# SCH_USB-hub-version-2_2024-07-09.net
KiCad netlist of a schematic drawn in EasyEDA
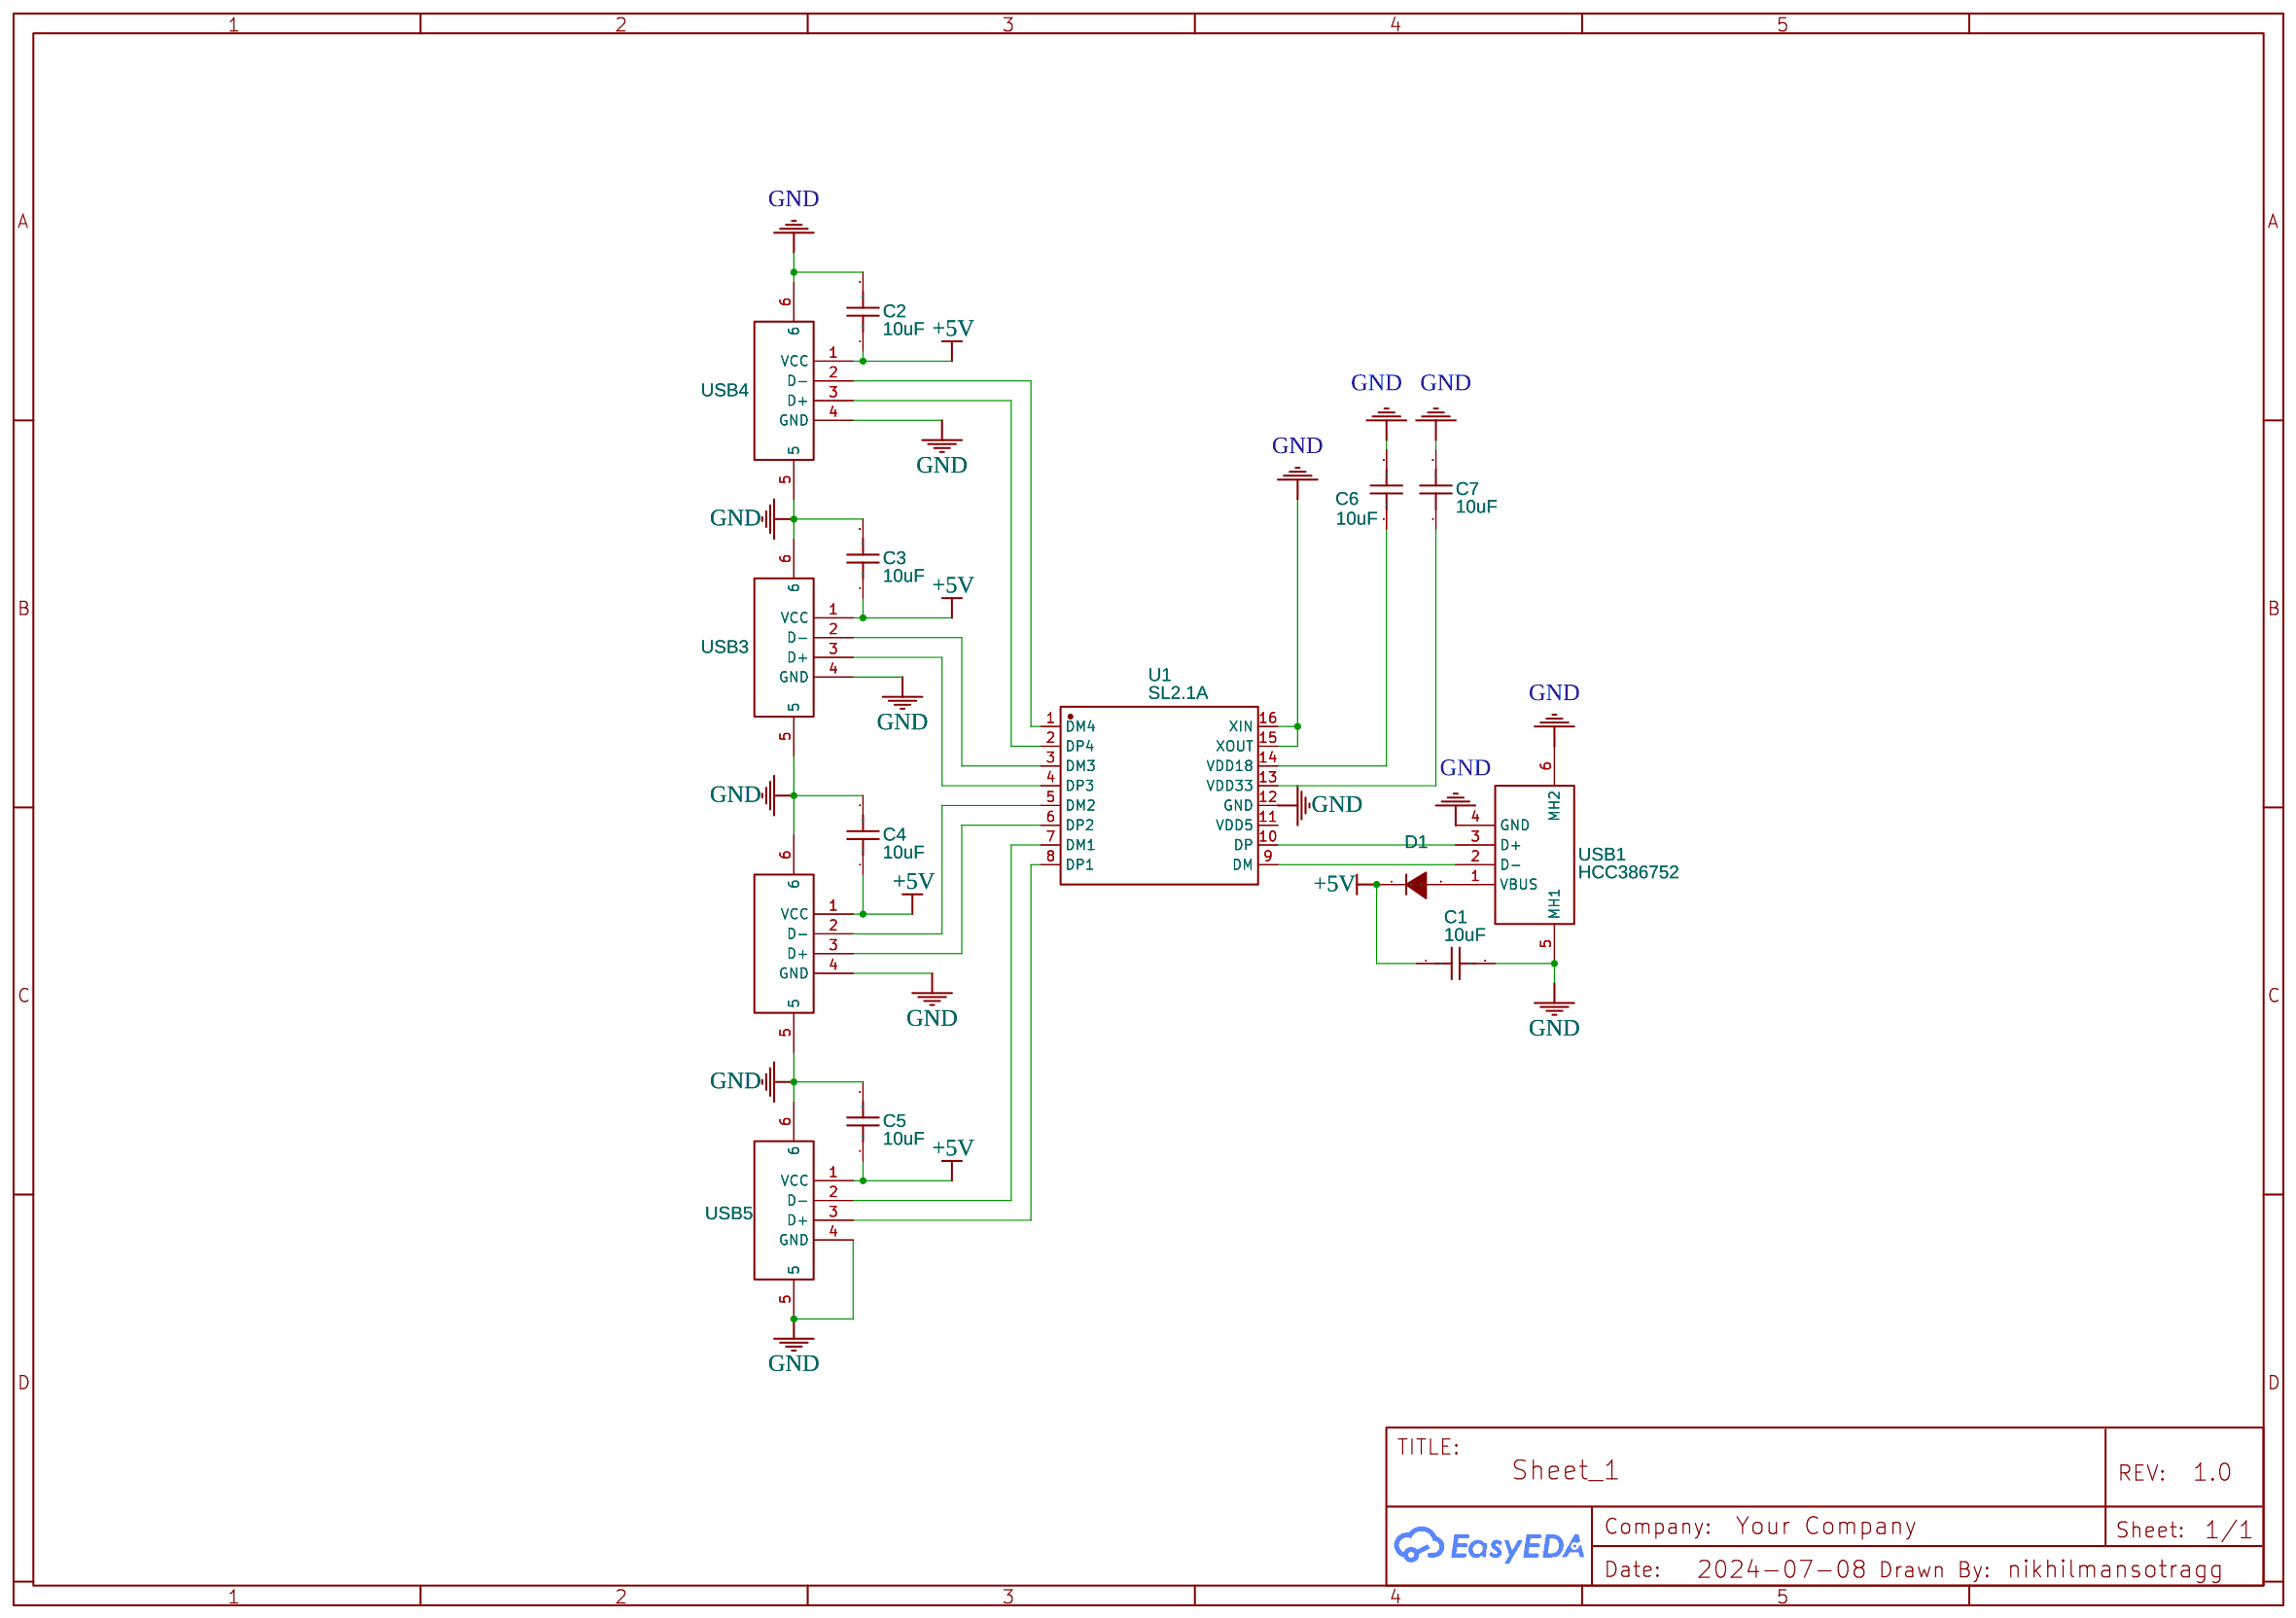
[diagram p0: schematic sheet]

(export (version "E")
  (design (tool "Eeschema 10.0.6"))
  (components
    (comp (ref "C1")
      (value "10uF")
      (fields
        (field (name "Manufacturer Part") "CL10A106KP8NNNC")
        (field (name "Manufacturer") "SAMSUNG(三星)")
      )
      (libsource (lib "") (part "CL10A106KP8NNNC_1"))
    )
    (comp (ref "C2")
      (value "10uF")
      (fields
        (field (name "Manufacturer Part") "CL10A106KP8NNNC")
        (field (name "Manufacturer") "SAMSUNG(三星)")
      )
      (libsource (lib "") (part "CL10A106KP8NNNC"))
    )
    (comp (ref "C3")
      (value "10uF")
      (fields
        (field (name "Manufacturer Part") "CL10A106KP8NNNC")
        (field (name "Manufacturer") "SAMSUNG(三星)")
      )
      (libsource (lib "") (part "CL10A106KP8NNNC"))
    )
    (comp (ref "C4")
      (value "10uF")
      (fields
        (field (name "Manufacturer Part") "CL10A106KP8NNNC")
        (field (name "Manufacturer") "SAMSUNG(三星)")
      )
      (libsource (lib "") (part "CL10A106KP8NNNC"))
    )
    (comp (ref "C5")
      (value "10uF")
      (fields
        (field (name "Manufacturer Part") "CL10A106KP8NNNC")
        (field (name "Manufacturer") "SAMSUNG(三星)")
      )
      (libsource (lib "") (part "CL10A106KP8NNNC"))
    )
    (comp (ref "C6")
      (value "10uF")
      (fields
        (field (name "Manufacturer Part") "CL10A106KP8NNNC")
        (field (name "Manufacturer") "SAMSUNG(三星)")
      )
      (libsource (lib "") (part "CL10A106KP8NNNC"))
    )
    (comp (ref "C7")
      (value "10uF")
      (fields
        (field (name "Manufacturer Part") "CL10A106KP8NNNC")
        (field (name "Manufacturer") "SAMSUNG(三星)")
      )
      (libsource (lib "") (part "CL10A106KP8NNNC"))
    )
    (comp (ref "D1")
      (value "NSR0320MW2T1G")
      (fields (field (name "Manufacturer") "onsemi(安森美)"))
      (libsource (lib "") (part "NSR0320MW2T1G"))
    )
    (comp (ref "U1")
      (value "SL2.1A")
      (fields (field (name "Manufacturer") "CoreChips(和芯润德)"))
      (libsource (lib "") (part "SL2.1A"))
    )
    (comp (ref "USB1")
      (value "HCC386752")
      (fields (field (name "Manufacturer Part") "U-USBAR04P-M003") (field (name "Manufacturer") "Ckmtw(灿科盟)"))
      (libsource (lib "") (part "HCC386752"))
    )
    (comp (ref "USB2")
      (value "USB-AF-90-14.4X13.6-H7.0-DIP")
      (fields (field (name "Manufacturer Part") "903-131A1011D10100") (field (name "Manufacturer") "精拓金"))
      (libsource (lib "") (part "USB-AF-90-14.4X13.6-H7.0-DIP"))
    )
    (comp (ref "USB3")
      (value "USB-AF-90-14.4X13.6-H7.0-DIP")
      (fields (field (name "Manufacturer Part") "903-131A1011D10100") (field (name "Manufacturer") "精拓金"))
      (libsource (lib "") (part "USB-AF-90-14.4X13.6-H7.0-DIP"))
    )
    (comp (ref "USB4")
      (value "USB-AF-90-14.4X13.6-H7.0-DIP")
      (fields (field (name "Manufacturer Part") "903-131A1011D10100") (field (name "Manufacturer") "精拓金"))
      (libsource (lib "") (part "USB-AF-90-14.4X13.6-H7.0-DIP"))
    )
    (comp (ref "USB5")
      (value "USB-AF-90-14.4X13.6-H7.0-DIP")
      (fields (field (name "Manufacturer Part") "903-131A1011D10100") (field (name "Manufacturer") "精拓金"))
      (libsource (lib "") (part "USB-AF-90-14.4X13.6-H7.0-DIP"))
    )
  )
  (nets
    (net (code "1") (name "+5V") (class "Default")
      (node (ref "C1") (pin "1") (pinfunction "1_1") (pintype "unspecified"))
      (node (ref "C2") (pin "1") (pinfunction "1_1") (pintype "unspecified"))
      (node (ref "C3") (pin "1") (pinfunction "1_1") (pintype "unspecified"))
      (node (ref "C4") (pin "1") (pinfunction "1_1") (pintype "unspecified"))
      (node (ref "C5") (pin "1") (pinfunction "1_1") (pintype "unspecified"))
      (node (ref "D1") (pin "1") (pinfunction "C_1") (pintype "unspecified"))
      (node (ref "USB2") (pin "1") (pinfunction "VCC_1") (pintype "unspecified"))
      (node (ref "USB3") (pin "1") (pinfunction "VCC_1") (pintype "unspecified"))
      (node (ref "USB4") (pin "1") (pinfunction "VCC_1") (pintype "unspecified"))
      (node (ref "USB5") (pin "1") (pinfunction "VCC_1") (pintype "unspecified"))
    )
    (net (code "2") (name "GND") (class "Default")
      (node (ref "C1") (pin "2") (pinfunction "2_2") (pintype "unspecified"))
      (node (ref "C2") (pin "2") (pinfunction "2_2") (pintype "unspecified"))
      (node (ref "C3") (pin "2") (pinfunction "2_2") (pintype "unspecified"))
      (node (ref "C4") (pin "2") (pinfunction "2_2") (pintype "unspecified"))
      (node (ref "C5") (pin "2") (pinfunction "2_2") (pintype "unspecified"))
      (node (ref "C6") (pin "2") (pinfunction "2_2") (pintype "unspecified"))
      (node (ref "C7") (pin "2") (pinfunction "2_2") (pintype "unspecified"))
      (node (ref "U1") (pin "12") (pinfunction "GND_12") (pintype "unspecified"))
      (node (ref "U1") (pin "15") (pinfunction "XOUT_15") (pintype "unspecified"))
      (node (ref "U1") (pin "16") (pinfunction "XIN_16") (pintype "unspecified"))
      (node (ref "USB1") (pin "4") (pinfunction "GND_4") (pintype "unspecified"))
      (node (ref "USB1") (pin "5") (pinfunction "MH1_5") (pintype "unspecified"))
      (node (ref "USB1") (pin "6") (pinfunction "MH2_6") (pintype "unspecified"))
      (node (ref "USB2") (pin "4") (pinfunction "GND_4") (pintype "unspecified"))
      (node (ref "USB2") (pin "5") (pinfunction "5_5") (pintype "unspecified"))
      (node (ref "USB2") (pin "6") (pinfunction "6_6") (pintype "unspecified"))
      (node (ref "USB3") (pin "4") (pinfunction "GND_4") (pintype "unspecified"))
      (node (ref "USB3") (pin "5") (pinfunction "5_5") (pintype "unspecified"))
      (node (ref "USB3") (pin "6") (pinfunction "6_6") (pintype "unspecified"))
      (node (ref "USB4") (pin "4") (pinfunction "GND_4") (pintype "unspecified"))
      (node (ref "USB4") (pin "5") (pinfunction "5_5") (pintype "unspecified"))
      (node (ref "USB4") (pin "6") (pinfunction "6_6") (pintype "unspecified"))
      (node (ref "USB5") (pin "4") (pinfunction "GND_4") (pintype "unspecified"))
      (node (ref "USB5") (pin "5") (pinfunction "5_5") (pintype "unspecified"))
      (node (ref "USB5") (pin "6") (pinfunction "6_6") (pintype "unspecified"))
    )
    (net (code "3") (name "Net-(D1-A)") (class "Default")
      (node (ref "D1") (pin "2") (pinfunction "A_2") (pintype "unspecified"))
      (node (ref "USB1") (pin "1") (pinfunction "VBUS_1") (pintype "unspecified"))
    )
    (net (code "4") (name "Net-(U1-DM)") (class "Default")
      (node (ref "U1") (pin "9") (pinfunction "DM_9") (pintype "unspecified"))
      (node (ref "USB1") (pin "2") (pinfunction "D-_2") (pintype "unspecified"))
    )
    (net (code "5") (name "Net-(U1-DM1)") (class "Default")
      (node (ref "U1") (pin "7") (pinfunction "DM1_7") (pintype "unspecified"))
      (node (ref "USB5") (pin "2") (pinfunction "D-_2") (pintype "unspecified"))
    )
    (net (code "6") (name "Net-(U1-DM2)") (class "Default")
      (node (ref "U1") (pin "5") (pinfunction "DM2_5") (pintype "unspecified"))
      (node (ref "USB2") (pin "2") (pinfunction "D-_2") (pintype "unspecified"))
    )
    (net (code "7") (name "Net-(U1-DM3)") (class "Default")
      (node (ref "U1") (pin "3") (pinfunction "DM3_3") (pintype "unspecified"))
      (node (ref "USB3") (pin "2") (pinfunction "D-_2") (pintype "unspecified"))
    )
    (net (code "8") (name "Net-(U1-DM4)") (class "Default")
      (node (ref "U1") (pin "1") (pinfunction "DM4_1") (pintype "unspecified"))
      (node (ref "USB4") (pin "2") (pinfunction "D-_2") (pintype "unspecified"))
    )
    (net (code "9") (name "Net-(U1-DP)") (class "Default")
      (node (ref "U1") (pin "10") (pinfunction "DP_10") (pintype "unspecified"))
      (node (ref "USB1") (pin "3") (pinfunction "D+_3") (pintype "unspecified"))
    )
    (net (code "10") (name "Net-(U1-DP1)") (class "Default")
      (node (ref "U1") (pin "8") (pinfunction "DP1_8") (pintype "unspecified"))
      (node (ref "USB5") (pin "3") (pinfunction "D+_3") (pintype "unspecified"))
    )
    (net (code "11") (name "Net-(U1-DP2)") (class "Default")
      (node (ref "U1") (pin "6") (pinfunction "DP2_6") (pintype "unspecified"))
      (node (ref "USB2") (pin "3") (pinfunction "D+_3") (pintype "unspecified"))
    )
    (net (code "12") (name "Net-(U1-DP3)") (class "Default")
      (node (ref "U1") (pin "4") (pinfunction "DP3_4") (pintype "unspecified"))
      (node (ref "USB3") (pin "3") (pinfunction "D+_3") (pintype "unspecified"))
    )
    (net (code "13") (name "Net-(U1-DP4)") (class "Default")
      (node (ref "U1") (pin "2") (pinfunction "DP4_2") (pintype "unspecified"))
      (node (ref "USB4") (pin "3") (pinfunction "D+_3") (pintype "unspecified"))
    )
    (net (code "14") (name "Net-(U1-VDD18)") (class "Default")
      (node (ref "C6") (pin "1") (pinfunction "1_1") (pintype "unspecified"))
      (node (ref "U1") (pin "14") (pinfunction "VDD18_14") (pintype "unspecified"))
    )
    (net (code "15") (name "Net-(U1-VDD33)") (class "Default")
      (node (ref "C7") (pin "1") (pinfunction "1_1") (pintype "unspecified"))
      (node (ref "U1") (pin "13") (pinfunction "VDD33_13") (pintype "unspecified"))
    )
    (net (code "16") (name "unconnected-(U1-VDD5-Pad11)") (class "Default")
      (node (ref "U1") (pin "11") (pinfunction "VDD5_11") (pintype "unspecified"))
    )
  )
)
